# plataforma_sensores.net
KiCad netlist of a schematic drawn in EasyEDA
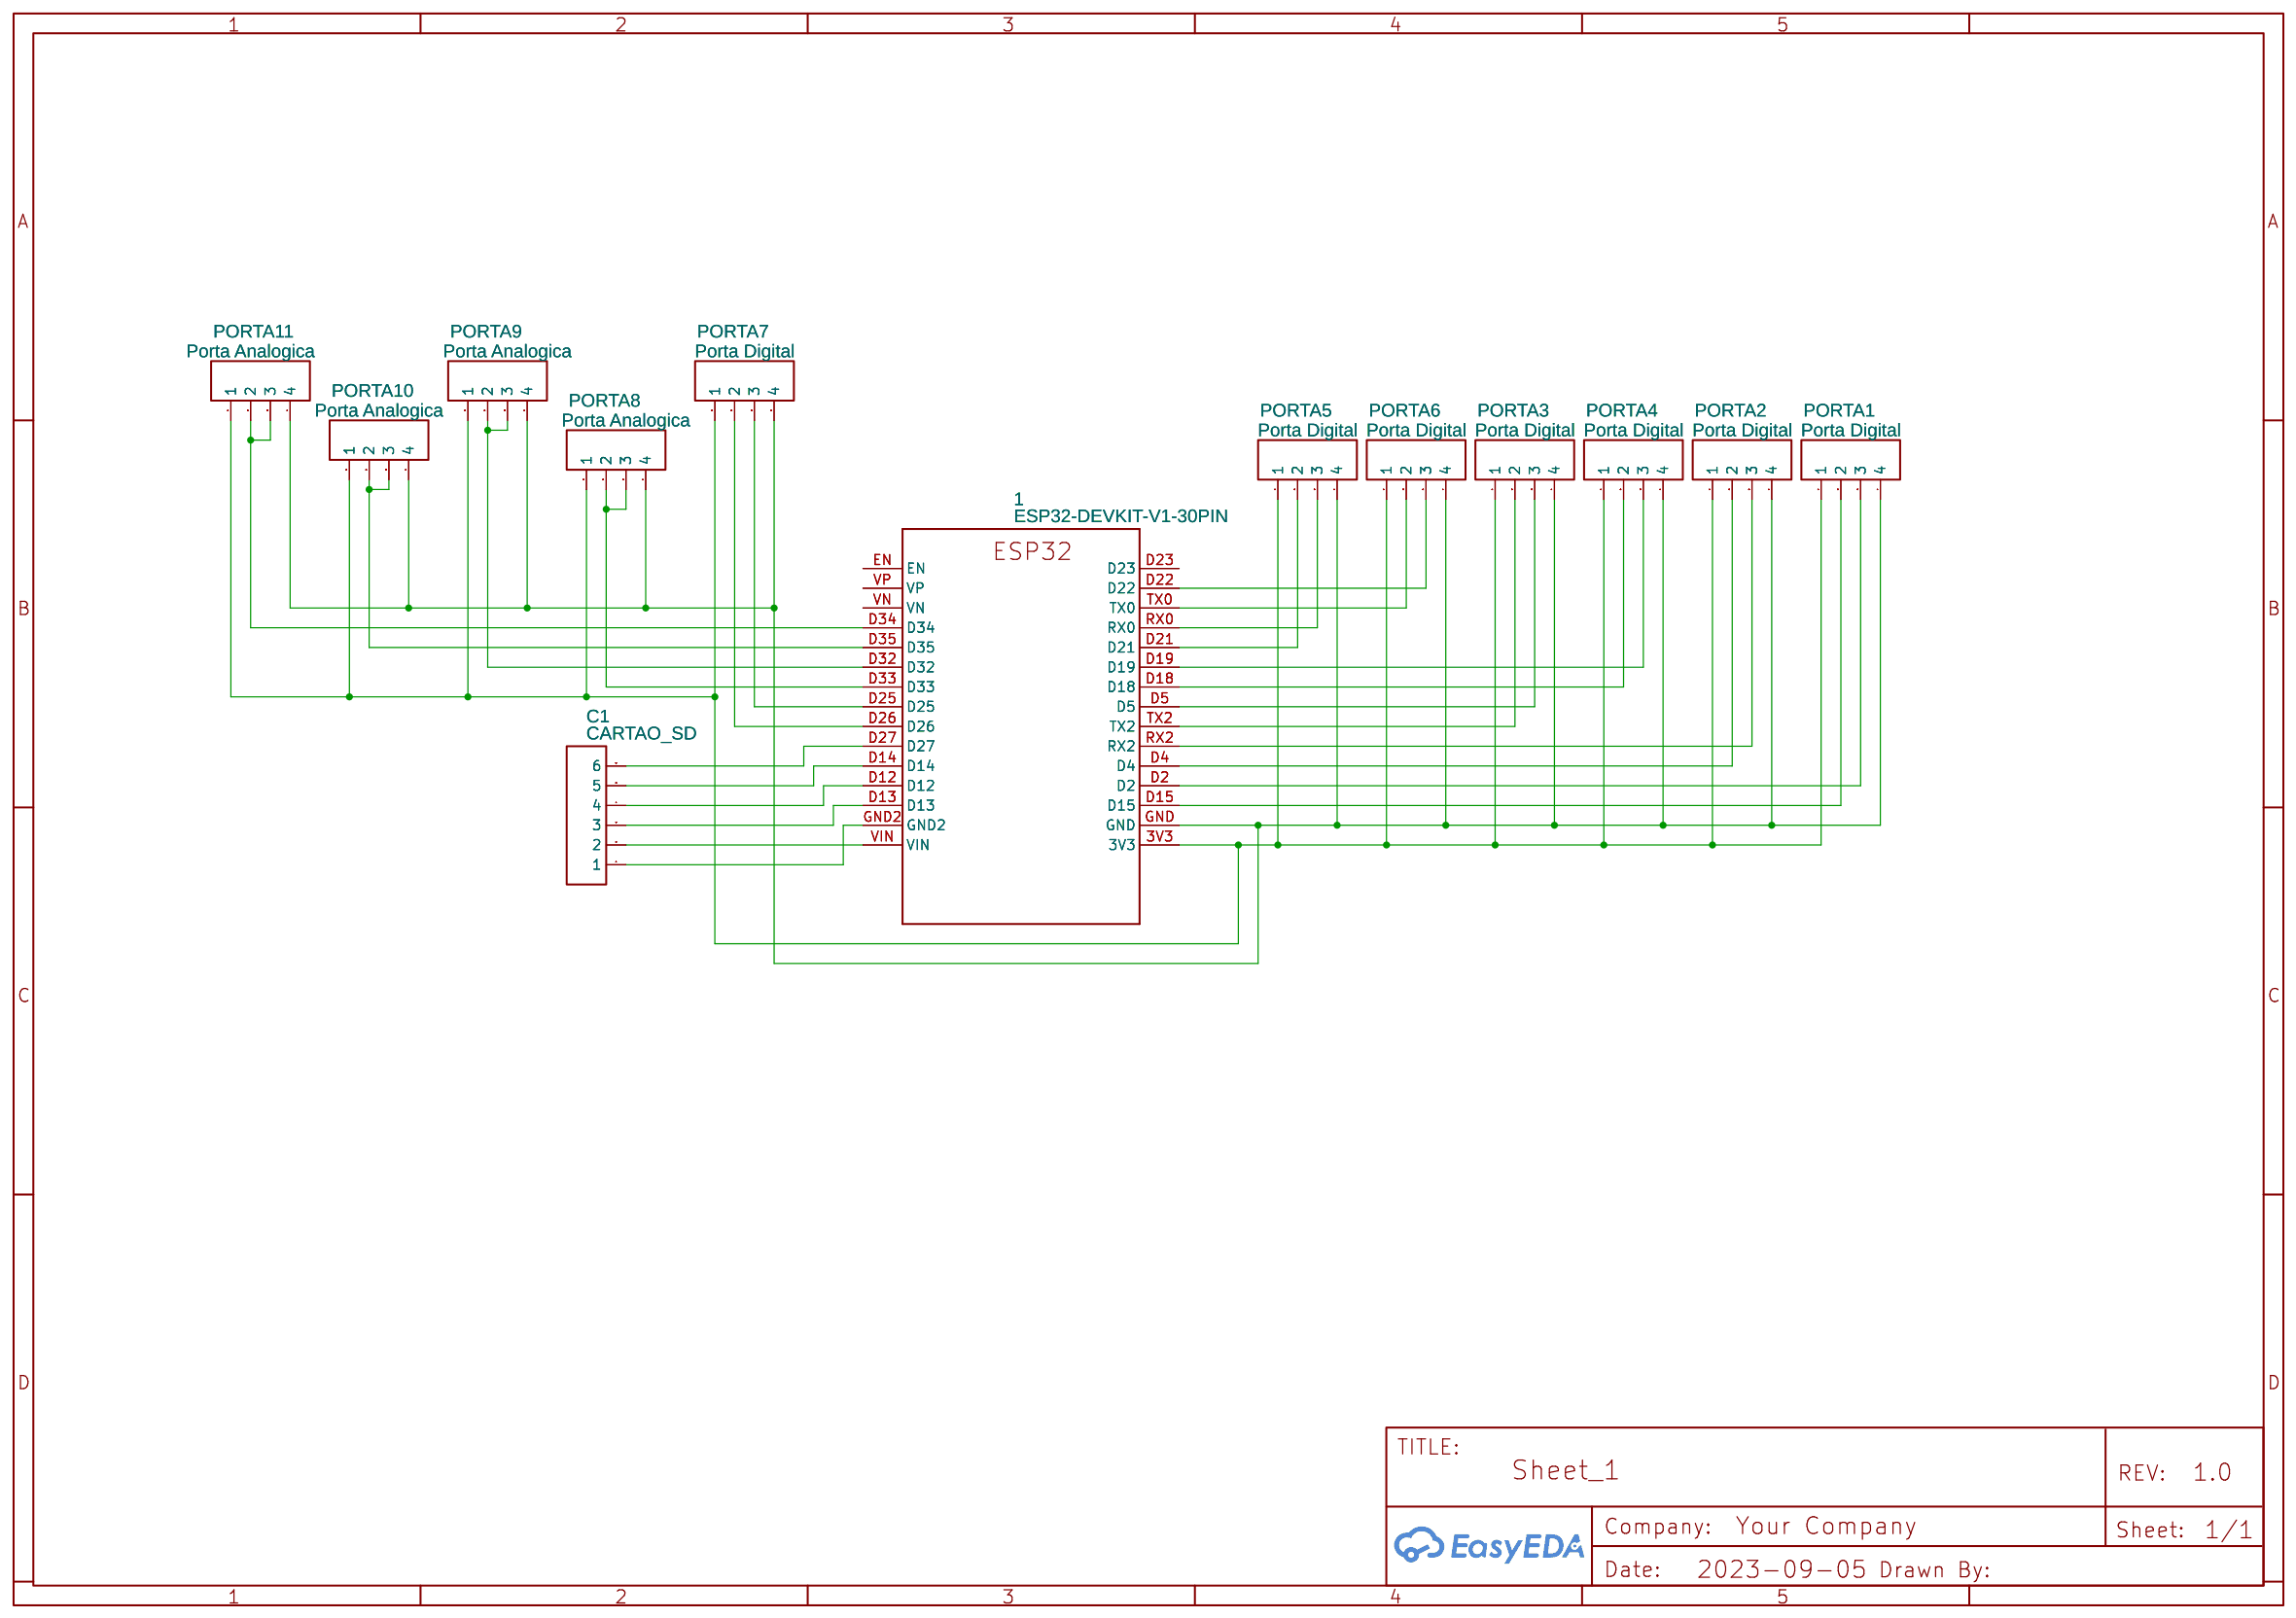
[diagram p0: schematic sheet]

(export (version "E")
  (design (tool "Eeschema 10.0.6"))
  (components
    (comp (ref "1") (value "ESP32-DEVKIT-V1-30PIN") (libsource (lib "") (part "ESP32-DEVKIT-V1-30PIN")))
    (comp (ref "C1") (value "CARTAO_SD") (libsource (lib "") (part "HDR-F-2.54_1x6")))
    (comp (ref "PORTA1") (value "Porta Digital") (libsource (lib "") (part "HDR-F-2.54_1x4")))
    (comp (ref "PORTA2") (value "Porta Digital") (libsource (lib "") (part "HDR-F-2.54_1x4")))
    (comp (ref "PORTA3") (value "Porta Digital") (libsource (lib "") (part "HDR-F-2.54_1x4")))
    (comp (ref "PORTA4") (value "Porta Digital") (libsource (lib "") (part "HDR-F-2.54_1x4")))
    (comp (ref "PORTA5") (value "Porta Digital") (libsource (lib "") (part "HDR-F-2.54_1x4")))
    (comp (ref "PORTA6") (value "Porta Digital") (libsource (lib "") (part "HDR-F-2.54_1x4")))
    (comp (ref "PORTA7") (value "Porta Digital") (libsource (lib "") (part "HDR-F-2.54_1x4")))
    (comp (ref "PORTA8") (value "Porta Analogica") (libsource (lib "") (part "HDR-F-2.54_1x4")))
    (comp (ref "PORTA9") (value "Porta Analogica") (libsource (lib "") (part "HDR-F-2.54_1x4")))
    (comp (ref "PORTA10") (value "Porta Analogica") (libsource (lib "") (part "HDR-F-2.54_1x4")))
    (comp (ref "PORTA11") (value "Porta Analogica") (libsource (lib "") (part "HDR-F-2.54_1x4")))
  )
  (nets
    (net (code "1") (name "Net-(1-Pad3V3)") (class "Default")
      (node (ref "1") (pin "3V3") (pinfunction "3V3_3V3") (pintype "unspecified"))
      (node (ref "PORTA1") (pin "1") (pinfunction "1_1") (pintype "unspecified"))
      (node (ref "PORTA10") (pin "1") (pinfunction "1_1") (pintype "unspecified"))
      (node (ref "PORTA11") (pin "1") (pinfunction "1_1") (pintype "unspecified"))
      (node (ref "PORTA2") (pin "1") (pinfunction "1_1") (pintype "unspecified"))
      (node (ref "PORTA3") (pin "1") (pinfunction "1_1") (pintype "unspecified"))
      (node (ref "PORTA4") (pin "1") (pinfunction "1_1") (pintype "unspecified"))
      (node (ref "PORTA5") (pin "1") (pinfunction "1_1") (pintype "unspecified"))
      (node (ref "PORTA6") (pin "1") (pinfunction "1_1") (pintype "unspecified"))
      (node (ref "PORTA7") (pin "1") (pinfunction "1_1") (pintype "unspecified"))
      (node (ref "PORTA8") (pin "1") (pinfunction "1_1") (pintype "unspecified"))
      (node (ref "PORTA9") (pin "1") (pinfunction "1_1") (pintype "unspecified"))
    )
    (net (code "2") (name "Net-(1-PadD2)") (class "Default")
      (node (ref "1") (pin "D2") (pinfunction "D2_D2") (pintype "unspecified"))
      (node (ref "PORTA1") (pin "3") (pinfunction "3_3") (pintype "unspecified"))
    )
    (net (code "3") (name "Net-(1-PadD4)") (class "Default")
      (node (ref "1") (pin "D4") (pinfunction "D4_D4") (pintype "unspecified"))
      (node (ref "PORTA2") (pin "2") (pinfunction "2_2") (pintype "unspecified"))
    )
    (net (code "4") (name "Net-(1-PadD5)") (class "Default")
      (node (ref "1") (pin "D5") (pinfunction "D5_D5") (pintype "unspecified"))
      (node (ref "PORTA3") (pin "3") (pinfunction "3_3") (pintype "unspecified"))
    )
    (net (code "5") (name "Net-(1-PadD12)") (class "Default")
      (node (ref "1") (pin "D12") (pinfunction "D12_D12") (pintype "unspecified"))
      (node (ref "C1") (pin "4") (pinfunction "4_4") (pintype "input"))
    )
    (net (code "6") (name "Net-(1-PadD13)") (class "Default")
      (node (ref "1") (pin "D13") (pinfunction "D13_D13") (pintype "unspecified"))
      (node (ref "C1") (pin "3") (pinfunction "3_3") (pintype "input"))
    )
    (net (code "7") (name "Net-(1-PadD14)") (class "Default")
      (node (ref "1") (pin "D14") (pinfunction "D14_D14") (pintype "unspecified"))
      (node (ref "C1") (pin "5") (pinfunction "5_5") (pintype "input"))
    )
    (net (code "8") (name "Net-(1-PadD15)") (class "Default")
      (node (ref "1") (pin "D15") (pinfunction "D15_D15") (pintype "unspecified"))
      (node (ref "PORTA1") (pin "2") (pinfunction "2_2") (pintype "unspecified"))
    )
    (net (code "9") (name "Net-(1-PadD18)") (class "Default")
      (node (ref "1") (pin "D18") (pinfunction "D18_D18") (pintype "unspecified"))
      (node (ref "PORTA4") (pin "2") (pinfunction "2_2") (pintype "unspecified"))
    )
    (net (code "10") (name "Net-(1-PadD19)") (class "Default")
      (node (ref "1") (pin "D19") (pinfunction "D19_D19") (pintype "unspecified"))
      (node (ref "PORTA4") (pin "3") (pinfunction "3_3") (pintype "unspecified"))
    )
    (net (code "11") (name "Net-(1-PadD21)") (class "Default")
      (node (ref "1") (pin "D21") (pinfunction "D21_D21") (pintype "unspecified"))
      (node (ref "PORTA5") (pin "2") (pinfunction "2_2") (pintype "unspecified"))
    )
    (net (code "12") (name "Net-(1-PadD22)") (class "Default")
      (node (ref "1") (pin "D22") (pinfunction "D22_D22") (pintype "unspecified"))
      (node (ref "PORTA6") (pin "3") (pinfunction "3_3") (pintype "unspecified"))
    )
    (net (code "13") (name "Net-(1-PadD25)") (class "Default")
      (node (ref "1") (pin "D25") (pinfunction "D25_D25") (pintype "unspecified"))
      (node (ref "PORTA7") (pin "3") (pinfunction "3_3") (pintype "unspecified"))
    )
    (net (code "14") (name "Net-(1-PadD26)") (class "Default")
      (node (ref "1") (pin "D26") (pinfunction "D26_D26") (pintype "unspecified"))
      (node (ref "PORTA7") (pin "2") (pinfunction "2_2") (pintype "unspecified"))
    )
    (net (code "15") (name "Net-(1-PadD27)") (class "Default")
      (node (ref "1") (pin "D27") (pinfunction "D27_D27") (pintype "unspecified"))
      (node (ref "C1") (pin "6") (pinfunction "6_6") (pintype "input"))
    )
    (net (code "16") (name "Net-(1-PadD32)") (class "Default")
      (node (ref "1") (pin "D32") (pinfunction "D32_D32") (pintype "unspecified"))
      (node (ref "PORTA9") (pin "2") (pinfunction "2_2") (pintype "unspecified"))
      (node (ref "PORTA9") (pin "3") (pinfunction "3_3") (pintype "unspecified"))
    )
    (net (code "17") (name "Net-(1-PadD33)") (class "Default")
      (node (ref "1") (pin "D33") (pinfunction "D33_D33") (pintype "unspecified"))
      (node (ref "PORTA8") (pin "2") (pinfunction "2_2") (pintype "unspecified"))
      (node (ref "PORTA8") (pin "3") (pinfunction "3_3") (pintype "unspecified"))
    )
    (net (code "18") (name "Net-(1-PadD34)") (class "Default")
      (node (ref "1") (pin "D34") (pinfunction "D34_D34") (pintype "unspecified"))
      (node (ref "PORTA11") (pin "2") (pinfunction "2_2") (pintype "unspecified"))
      (node (ref "PORTA11") (pin "3") (pinfunction "3_3") (pintype "unspecified"))
    )
    (net (code "19") (name "Net-(1-PadD35)") (class "Default")
      (node (ref "1") (pin "D35") (pinfunction "D35_D35") (pintype "unspecified"))
      (node (ref "PORTA10") (pin "2") (pinfunction "2_2") (pintype "unspecified"))
      (node (ref "PORTA10") (pin "3") (pinfunction "3_3") (pintype "unspecified"))
    )
    (net (code "20") (name "Net-(1-PadGND)") (class "Default")
      (node (ref "1") (pin "GND") (pinfunction "GND_GND") (pintype "unspecified"))
      (node (ref "PORTA1") (pin "4") (pinfunction "4_4") (pintype "unspecified"))
      (node (ref "PORTA10") (pin "4") (pinfunction "4_4") (pintype "unspecified"))
      (node (ref "PORTA11") (pin "4") (pinfunction "4_4") (pintype "unspecified"))
      (node (ref "PORTA2") (pin "4") (pinfunction "4_4") (pintype "unspecified"))
      (node (ref "PORTA3") (pin "4") (pinfunction "4_4") (pintype "unspecified"))
      (node (ref "PORTA4") (pin "4") (pinfunction "4_4") (pintype "unspecified"))
      (node (ref "PORTA5") (pin "4") (pinfunction "4_4") (pintype "unspecified"))
      (node (ref "PORTA6") (pin "4") (pinfunction "4_4") (pintype "unspecified"))
      (node (ref "PORTA7") (pin "4") (pinfunction "4_4") (pintype "unspecified"))
      (node (ref "PORTA8") (pin "4") (pinfunction "4_4") (pintype "unspecified"))
      (node (ref "PORTA9") (pin "4") (pinfunction "4_4") (pintype "unspecified"))
    )
    (net (code "21") (name "Net-(1-PadGND2)") (class "Default")
      (node (ref "1") (pin "GND2") (pinfunction "GND2_GND2") (pintype "unspecified"))
      (node (ref "C1") (pin "1") (pinfunction "1_1") (pintype "input"))
    )
    (net (code "22") (name "Net-(1-PadRX0)") (class "Default")
      (node (ref "1") (pin "RX0") (pinfunction "RX0_RX0") (pintype "unspecified"))
      (node (ref "PORTA5") (pin "3") (pinfunction "3_3") (pintype "unspecified"))
    )
    (net (code "23") (name "Net-(1-PadRX2)") (class "Default")
      (node (ref "1") (pin "RX2") (pinfunction "RX2_RX2") (pintype "unspecified"))
      (node (ref "PORTA2") (pin "3") (pinfunction "3_3") (pintype "unspecified"))
    )
    (net (code "24") (name "Net-(1-PadTX0)") (class "Default")
      (node (ref "1") (pin "TX0") (pinfunction "TX0_TX0") (pintype "unspecified"))
      (node (ref "PORTA6") (pin "2") (pinfunction "2_2") (pintype "unspecified"))
    )
    (net (code "25") (name "Net-(1-PadTX2)") (class "Default")
      (node (ref "1") (pin "TX2") (pinfunction "TX2_TX2") (pintype "unspecified"))
      (node (ref "PORTA3") (pin "2") (pinfunction "2_2") (pintype "unspecified"))
    )
    (net (code "26") (name "Net-(1-PadVIN)") (class "Default")
      (node (ref "1") (pin "VIN") (pinfunction "VIN_VIN") (pintype "unspecified"))
      (node (ref "C1") (pin "2") (pinfunction "2_2") (pintype "input"))
    )
    (net (code "27") (name "unconnected-(1-PadD23)") (class "Default")
      (node (ref "1") (pin "D23") (pinfunction "D23_D23") (pintype "unspecified"))
    )
    (net (code "28") (name "unconnected-(1-PadEN)") (class "Default")
      (node (ref "1") (pin "EN") (pinfunction "EN_EN") (pintype "unspecified"))
    )
    (net (code "29") (name "unconnected-(1-PadVN)") (class "Default")
      (node (ref "1") (pin "VN") (pinfunction "VN_VN") (pintype "unspecified"))
    )
    (net (code "30") (name "unconnected-(1-PadVP)") (class "Default")
      (node (ref "1") (pin "VP") (pinfunction "VP_VP") (pintype "unspecified"))
    )
  )
)
